# USB.net
KiCad netlist of a schematic drawn in Altium Designer
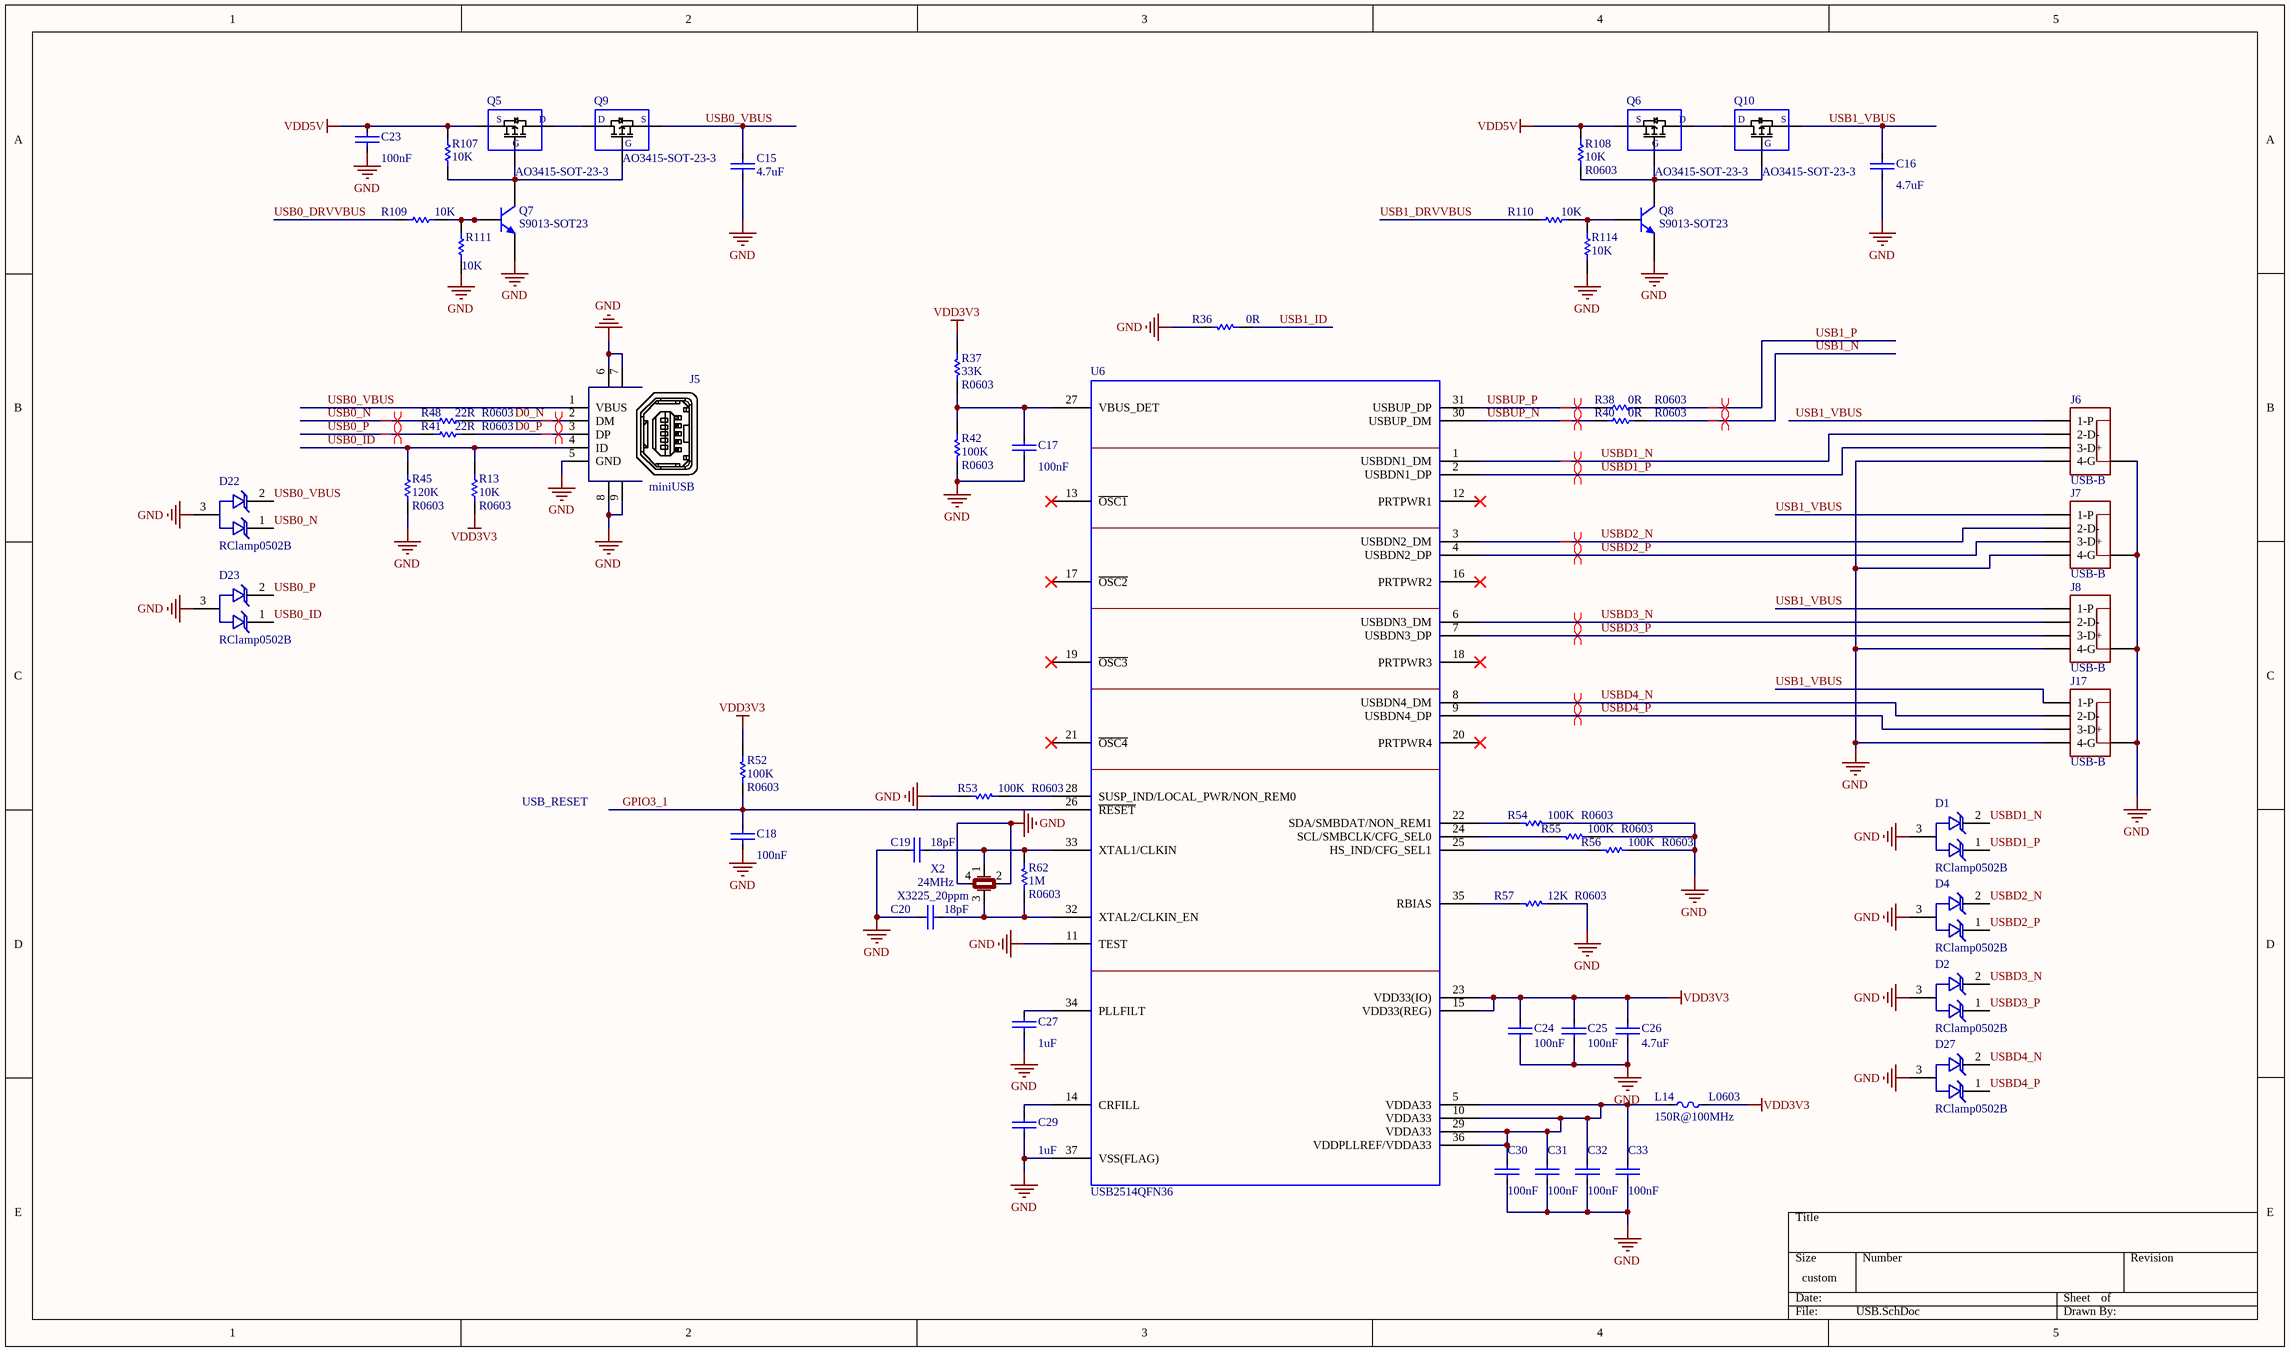
[diagram p0: USB.SchDoc]

(export (version "E")
  (design (tool "Eeschema 10.0.6"))
  (components
    (comp (ref "C15") (value "4.7uF") (footprint "C0603_M1608") (libsource (lib "OK335xD") (part "CAP_1")))
    (comp (ref "C16") (value "4.7uF") (footprint "C0603_M1608") (libsource (lib "OK335xD") (part "CAP_1")))
    (comp (ref "C17") (value "100nF") (footprint "C0603_M1608") (libsource (lib "OK335xD") (part "CAP_1")))
    (comp (ref "C18") (value "100nF") (footprint "C0603_M1608") (libsource (lib "OK335xD") (part "CAP_1")))
    (comp (ref "C19") (value "18pF") (footprint "C0603_M1608") (libsource (lib "OK335xD") (part "CAP_1")))
    (comp (ref "C20") (value "18pF") (footprint "C0603_M1608") (libsource (lib "OK335xD") (part "CAP_1")))
    (comp (ref "C23") (value "100nF") (footprint "C0603_M1608") (libsource (lib "OK335xD") (part "CAP_1")))
    (comp (ref "C24") (value "100nF") (footprint "C0603_M1608") (libsource (lib "OK335xD") (part "CAP_1")))
    (comp (ref "C25") (value "100nF") (footprint "C0603_M1608") (libsource (lib "OK335xD") (part "CAP_1")))
    (comp (ref "C26") (value "4.7uF") (footprint "C0603_M1608") (libsource (lib "OK335xD") (part "CAP_1")))
    (comp (ref "C27") (value "1uF") (footprint "C0603_M1608") (libsource (lib "OK335xD") (part "CAP_1")))
    (comp (ref "C29") (value "1uF") (footprint "C0603_M1608") (libsource (lib "OK335xD") (part "CAP_1")))
    (comp (ref "C30") (value "100nF") (footprint "C0603_M1608") (libsource (lib "OK335xD") (part "CAP_1")))
    (comp (ref "C31") (value "100nF") (footprint "C0603_M1608") (libsource (lib "OK335xD") (part "CAP_1")))
    (comp (ref "C32") (value "100nF") (footprint "C0603_M1608") (libsource (lib "OK335xD") (part "CAP_1")))
    (comp (ref "C33") (value "100nF") (footprint "C0603_M1608") (libsource (lib "OK335xD") (part "CAP_1")))
    (comp (ref "D1")
      (value "RClamp0502B")
      (footprint "SOT-523")
      (fields (field (name "Comment") "LCTVS"))
      (libsource (lib "Sch") (part "LCTVS"))
    )
    (comp (ref "D2")
      (value "RClamp0502B")
      (footprint "SOT-523")
      (fields (field (name "Comment") "LCTVS"))
      (libsource (lib "Sch") (part "LCTVS"))
    )
    (comp (ref "D4")
      (value "RClamp0502B")
      (footprint "SOT-523")
      (fields (field (name "Comment") "LCTVS"))
      (libsource (lib "Sch") (part "LCTVS"))
    )
    (comp (ref "D22")
      (value "RClamp0502B")
      (footprint "SOT-523")
      (fields (field (name "Comment") "LCTVS"))
      (libsource (lib "Sch") (part "LCTVS"))
    )
    (comp (ref "D23")
      (value "RClamp0502B")
      (footprint "SOT-523")
      (fields (field (name "Comment") "LCTVS"))
      (libsource (lib "Sch") (part "LCTVS"))
    )
    (comp (ref "D27")
      (value "RClamp0502B")
      (footprint "SOT-523")
      (fields (field (name "Comment") "LCTVS"))
      (libsource (lib "Sch") (part "LCTVS"))
    )
    (comp (ref "J5")
      (value "miniUSB")
      (footprint "MiniUSB")
      (libsource (lib "AM335X_bottom") (part "miniUSB"))
    )
    (comp (ref "J6") (value "USB-B") (footprint "USB-C") (libsource (lib "OK335xD") (part "USB_B")))
    (comp (ref "J7") (value "USB-B") (footprint "USB-C") (libsource (lib "OK335xD") (part "USB_B")))
    (comp (ref "J8") (value "USB-B") (footprint "USB-C") (libsource (lib "OK335xD") (part "USB_B")))
    (comp (ref "J17") (value "USB-B") (footprint "USB-C") (libsource (lib "OK335xD") (part "USB_B")))
    (comp (ref "L14")
      (value "150R@100MHz")
      (footprint "L0603_M1608")
      (description "0603")
      (fields (field (name "ALTIUM_VALUE") "L0603"))
      (libsource (lib "S5PV210_core") (part "BEADS"))
    )
    (comp (ref "Q5")
      (value "AO3415-SOT-23-3")
      (footprint "SOT23")
      (libsource (lib "OK335xD") (part "AO3415"))
    )
    (comp (ref "Q6")
      (value "AO3415-SOT-23-3")
      (footprint "SOT23")
      (libsource (lib "OK335xD") (part "AO3415"))
    )
    (comp (ref "Q7") (value "S9013-SOT23") (footprint "SOT23") (libsource (lib "Sch") (part "S9013")))
    (comp (ref "Q8") (value "S9013-SOT23") (footprint "SOT23") (libsource (lib "Sch") (part "S9013")))
    (comp (ref "Q9")
      (value "AO3415-SOT-23-3")
      (footprint "SOT23")
      (libsource (lib "OK335xD") (part "AO3415"))
    )
    (comp (ref "Q10")
      (value "AO3415-SOT-23-3")
      (footprint "SOT23")
      (libsource (lib "OK335xD") (part "AO3415"))
    )
    (comp (ref "R13")
      (value "10K")
      (footprint "R0603_M1608")
      (description "R0603")
      (fields (field (name "ALTIUM_VALUE") "R0603") (field (name "PUBLISHER") "Altium Limited"))
      (libsource (lib "Miscellaneous Devices") (part "Res1"))
    )
    (comp (ref "R36")
      (value "0R")
      (footprint "R0603_M1608")
      (description "R0603")
      (fields (field (name "PUBLISHER") "Altium Limited"))
      (libsource (lib "Miscellaneous Devices") (part "Res1"))
    )
    (comp (ref "R37")
      (value "33K")
      (footprint "R0603_M1608")
      (description "R0603")
      (fields (field (name "ALTIUM_VALUE") "R0603") (field (name "PUBLISHER") "Altium Limited"))
      (libsource (lib "Miscellaneous Devices") (part "Res1"))
    )
    (comp (ref "R38")
      (value "0R")
      (footprint "R0603_M1608")
      (description "R0603")
      (fields (field (name "ALTIUM_VALUE") "R0603") (field (name "PUBLISHER") "Altium Limited"))
      (libsource (lib "Miscellaneous Devices") (part "Res1"))
    )
    (comp (ref "R40")
      (value "0R")
      (footprint "R0603_M1608")
      (description "R0603")
      (fields (field (name "ALTIUM_VALUE") "R0603") (field (name "PUBLISHER") "Altium Limited"))
      (libsource (lib "Miscellaneous Devices") (part "Res1"))
    )
    (comp (ref "R41")
      (value "22R")
      (footprint "R0603_M1608")
      (description "R0603")
      (fields (field (name "ALTIUM_VALUE") "R0603") (field (name "PUBLISHER") "Altium Limited"))
      (libsource (lib "Miscellaneous Devices") (part "Res1"))
    )
    (comp (ref "R42")
      (value "100K")
      (footprint "R0603_M1608")
      (description "R0603")
      (fields (field (name "ALTIUM_VALUE") "R0603") (field (name "PUBLISHER") "Altium Limited"))
      (libsource (lib "Miscellaneous Devices") (part "Res1"))
    )
    (comp (ref "R45")
      (value "120K")
      (footprint "R0603_M1608")
      (description "R0603")
      (fields (field (name "ALTIUM_VALUE") "R0603") (field (name "PUBLISHER") "Altium Limited"))
      (libsource (lib "Miscellaneous Devices") (part "Res1"))
    )
    (comp (ref "R48")
      (value "22R")
      (footprint "R0603_M1608")
      (description "R0603")
      (fields (field (name "ALTIUM_VALUE") "R0603") (field (name "PUBLISHER") "Altium Limited"))
      (libsource (lib "Miscellaneous Devices") (part "Res1"))
    )
    (comp (ref "R52")
      (value "100K")
      (footprint "R0603_M1608")
      (description "R0603")
      (fields (field (name "ALTIUM_VALUE") "R0603") (field (name "PUBLISHER") "Altium Limited"))
      (libsource (lib "Miscellaneous Devices") (part "Res1"))
    )
    (comp (ref "R53")
      (value "100K")
      (footprint "R0603_M1608")
      (description "R0603")
      (fields (field (name "ALTIUM_VALUE") "R0603") (field (name "PUBLISHER") "Altium Limited"))
      (libsource (lib "Miscellaneous Devices") (part "Res1"))
    )
    (comp (ref "R54")
      (value "100K")
      (footprint "R0603_M1608")
      (description "R0603")
      (fields (field (name "ALTIUM_VALUE") "R0603") (field (name "PUBLISHER") "Altium Limited"))
      (libsource (lib "Miscellaneous Devices") (part "Res1"))
    )
    (comp (ref "R55")
      (value "100K")
      (footprint "R0603_M1608")
      (description "R0603")
      (fields (field (name "ALTIUM_VALUE") "R0603") (field (name "PUBLISHER") "Altium Limited"))
      (libsource (lib "Miscellaneous Devices") (part "Res1"))
    )
    (comp (ref "R56")
      (value "100K")
      (footprint "R0603_M1608")
      (description "R0603")
      (fields (field (name "ALTIUM_VALUE") "R0603") (field (name "PUBLISHER") "Altium Limited"))
      (libsource (lib "Miscellaneous Devices") (part "Res1"))
    )
    (comp (ref "R57")
      (value "12K")
      (footprint "R0603_M1608")
      (description "R0603")
      (fields (field (name "ALTIUM_VALUE") "R0603") (field (name "PUBLISHER") "Altium Limited"))
      (libsource (lib "Miscellaneous Devices") (part "Res1"))
    )
    (comp (ref "R62")
      (value "1M")
      (footprint "R0603_M1608")
      (description "R0603")
      (fields (field (name "ALTIUM_VALUE") "R0603") (field (name "PUBLISHER") "Altium Limited"))
      (libsource (lib "Miscellaneous Devices") (part "Res1"))
    )
    (comp (ref "R107")
      (value "10K")
      (footprint "R0603_M1608")
      (description "R0603")
      (fields (field (name "PUBLISHER") "Altium Limited"))
      (libsource (lib "Miscellaneous Devices") (part "Res1"))
    )
    (comp (ref "R108")
      (value "10K")
      (footprint "R0603_M1608")
      (description "R0603")
      (fields (field (name "ALTIUM_VALUE") "R0603") (field (name "PUBLISHER") "Altium Limited"))
      (libsource (lib "Miscellaneous Devices") (part "Res1"))
    )
    (comp (ref "R109")
      (value "10K")
      (footprint "R0603_M1608")
      (description "R0603")
      (fields (field (name "PUBLISHER") "Altium Limited"))
      (libsource (lib "Miscellaneous Devices") (part "Res1"))
    )
    (comp (ref "R110")
      (value "10K")
      (footprint "R0603_M1608")
      (description "R0603")
      (fields (field (name "PUBLISHER") "Altium Limited"))
      (libsource (lib "Miscellaneous Devices") (part "Res1"))
    )
    (comp (ref "R111")
      (value "10K")
      (footprint "R0603_M1608")
      (description "R0603")
      (fields (field (name "PUBLISHER") "Altium Limited"))
      (libsource (lib "Miscellaneous Devices") (part "Res1"))
    )
    (comp (ref "R114")
      (value "10K")
      (footprint "R0603_M1608")
      (description "R0603")
      (fields (field (name "PUBLISHER") "Altium Limited"))
      (libsource (lib "Miscellaneous Devices") (part "Res1"))
    )
    (comp (ref "U6")
      (value "USB2514QFN36")
      (footprint "QFN36(USB251x)")
      (libsource (lib "OK335xD") (part "USB2514QFN36"))
    )
    (comp (ref "X2")
      (value "24MHz")
      (footprint "Crystals_3225")
      (description "X3225_20ppm")
      (fields (field (name "ALTIUM_VALUE") "X3225_20ppm"))
      (libsource (lib "S5PV210_core") (part "XTAL"))
    )
  )
  (nets
    (net (code "1") (name "/D0_N") (class "Default")
      (node (ref "J5") (pin "2") (pinfunction "DM_2") (pintype "passive"))
      (node (ref "R48") (pin "2") (pinfunction "2_2") (pintype "passive"))
    )
    (net (code "2") (name "/D0_P") (class "Default")
      (node (ref "J5") (pin "3") (pinfunction "DP_3") (pintype "passive"))
      (node (ref "R41") (pin "2") (pinfunction "2_2") (pintype "passive"))
    )
    (net (code "3") (name "/GPIO3_1") (class "Default")
      (node (ref "C18") (pin "2") (pintype "passive"))
      (node (ref "R52") (pin "1") (pinfunction "1_1") (pintype "passive"))
      (node (ref "U6") (pin "26") (pinfunction "~{RESET}_26") (pintype "passive"))
    )
    (net (code "4") (name "/USB0_DRVVBUS") (class "Default")
      (node (ref "R109") (pin "2") (pinfunction "2_2") (pintype "passive"))
    )
    (net (code "5") (name "/USB0_ID") (class "Default")
      (node (ref "D23") (pin "1") (pinfunction "1_1") (pintype "passive"))
      (node (ref "J5") (pin "4") (pinfunction "ID_4") (pintype "passive"))
      (node (ref "R13") (pin "2") (pinfunction "2_2") (pintype "passive"))
      (node (ref "R45") (pin "2") (pinfunction "2_2") (pintype "passive"))
    )
    (net (code "6") (name "/USB0_N") (class "Default")
      (node (ref "D22") (pin "1") (pinfunction "1_1") (pintype "passive"))
      (node (ref "R48") (pin "1") (pinfunction "1_1") (pintype "passive"))
    )
    (net (code "7") (name "/USB0_P") (class "Default")
      (node (ref "D23") (pin "2") (pinfunction "2_2") (pintype "passive"))
      (node (ref "R41") (pin "1") (pinfunction "1_1") (pintype "passive"))
    )
    (net (code "8") (name "/USB0_VBUS") (class "Default")
      (node (ref "C15") (pin "1") (pintype "passive"))
      (node (ref "D22") (pin "2") (pinfunction "2_2") (pintype "passive"))
      (node (ref "J5") (pin "1") (pinfunction "VBUS_1") (pintype "passive"))
      (node (ref "Q9") (pin "2") (pinfunction "S_2") (pintype "passive"))
    )
    (net (code "9") (name "/USB1_DRVVBUS") (class "Default")
      (node (ref "R110") (pin "2") (pinfunction "2_2") (pintype "passive"))
    )
    (net (code "10") (name "/USB1_ID") (class "Default")
      (node (ref "R36") (pin "2") (pinfunction "2_2") (pintype "passive"))
    )
    (net (code "11") (name "/USB1_N") (class "Default")
      (node (ref "R40") (pin "2") (pinfunction "2_2") (pintype "passive"))
    )
    (net (code "12") (name "/USB1_P") (class "Default")
      (node (ref "R38") (pin "2") (pinfunction "2_2") (pintype "passive"))
    )
    (net (code "13") (name "/USB1_VBUS") (class "Default")
      (node (ref "C16") (pin "1") (pintype "passive"))
      (node (ref "J17") (pin "1") (pinfunction "1-P_1") (pintype "passive"))
      (node (ref "J6") (pin "1") (pinfunction "1-P_1") (pintype "passive"))
      (node (ref "J7") (pin "1") (pinfunction "1-P_1") (pintype "passive"))
      (node (ref "J8") (pin "1") (pinfunction "1-P_1") (pintype "passive"))
      (node (ref "Q10") (pin "2") (pinfunction "S_2") (pintype "passive"))
    )
    (net (code "14") (name "/USBD1_N") (class "Default")
      (node (ref "D1") (pin "2") (pinfunction "2_2") (pintype "passive"))
      (node (ref "J6") (pin "2") (pinfunction "2-D-_2") (pintype "passive"))
      (node (ref "U6") (pin "1") (pinfunction "USBDN1_DM_1") (pintype "passive"))
    )
    (net (code "15") (name "/USBD1_P") (class "Default")
      (node (ref "D1") (pin "1") (pinfunction "1_1") (pintype "passive"))
      (node (ref "J6") (pin "3") (pinfunction "3-D+_3") (pintype "passive"))
      (node (ref "U6") (pin "2") (pinfunction "USBDN1_DP_2") (pintype "passive"))
    )
    (net (code "16") (name "/USBD2_N") (class "Default")
      (node (ref "D4") (pin "2") (pinfunction "2_2") (pintype "passive"))
      (node (ref "J7") (pin "2") (pinfunction "2-D-_2") (pintype "passive"))
      (node (ref "U6") (pin "3") (pinfunction "USBDN2_DM_3") (pintype "passive"))
    )
    (net (code "17") (name "/USBD2_P") (class "Default")
      (node (ref "D4") (pin "1") (pinfunction "1_1") (pintype "passive"))
      (node (ref "J7") (pin "3") (pinfunction "3-D+_3") (pintype "passive"))
      (node (ref "U6") (pin "4") (pinfunction "USBDN2_DP_4") (pintype "passive"))
    )
    (net (code "18") (name "/USBD3_N") (class "Default")
      (node (ref "D2") (pin "2") (pinfunction "2_2") (pintype "passive"))
      (node (ref "J8") (pin "2") (pinfunction "2-D-_2") (pintype "passive"))
      (node (ref "U6") (pin "6") (pinfunction "USBDN3_DM_6") (pintype "passive"))
    )
    (net (code "19") (name "/USBD3_P") (class "Default")
      (node (ref "D2") (pin "1") (pinfunction "1_1") (pintype "passive"))
      (node (ref "J8") (pin "3") (pinfunction "3-D+_3") (pintype "passive"))
      (node (ref "U6") (pin "7") (pinfunction "USBDN3_DP_7") (pintype "passive"))
    )
    (net (code "20") (name "/USBD4_N") (class "Default")
      (node (ref "D27") (pin "2") (pinfunction "2_2") (pintype "passive"))
      (node (ref "J17") (pin "2") (pinfunction "2-D-_2") (pintype "passive"))
      (node (ref "U6") (pin "8") (pinfunction "USBDN4_DM_8") (pintype "passive"))
    )
    (net (code "21") (name "/USBD4_P") (class "Default")
      (node (ref "D27") (pin "1") (pinfunction "1_1") (pintype "passive"))
      (node (ref "J17") (pin "3") (pinfunction "3-D+_3") (pintype "passive"))
      (node (ref "U6") (pin "9") (pinfunction "USBDN4_DP_9") (pintype "passive"))
    )
    (net (code "22") (name "/USBUP_N") (class "Default")
      (node (ref "R40") (pin "1") (pinfunction "1_1") (pintype "passive"))
      (node (ref "U6") (pin "30") (pinfunction "USBUP_DM_30") (pintype "passive"))
    )
    (net (code "23") (name "/USBUP_P") (class "Default")
      (node (ref "R38") (pin "1") (pinfunction "1_1") (pintype "passive"))
      (node (ref "U6") (pin "31") (pinfunction "USBUP_DP_31") (pintype "passive"))
    )
    (net (code "24") (name "GND") (class "Default")
      (node (ref "C15") (pin "2") (pintype "passive"))
      (node (ref "C16") (pin "2") (pintype "passive"))
      (node (ref "C17") (pin "2") (pintype "passive"))
      (node (ref "C18") (pin "1") (pintype "passive"))
      (node (ref "C19") (pin "1") (pintype "passive"))
      (node (ref "C20") (pin "1") (pintype "passive"))
      (node (ref "C23") (pin "1") (pintype "passive"))
      (node (ref "C24") (pin "2") (pintype "passive"))
      (node (ref "C25") (pin "2") (pintype "passive"))
      (node (ref "C26") (pin "2") (pintype "passive"))
      (node (ref "C27") (pin "2") (pintype "passive"))
      (node (ref "C29") (pin "2") (pintype "passive"))
      (node (ref "C30") (pin "2") (pintype "passive"))
      (node (ref "C31") (pin "2") (pintype "passive"))
      (node (ref "C32") (pin "2") (pintype "passive"))
      (node (ref "C33") (pin "2") (pintype "passive"))
      (node (ref "D1") (pin "3") (pintype "passive"))
      (node (ref "D2") (pin "3") (pintype "passive"))
      (node (ref "D22") (pin "3") (pintype "passive"))
      (node (ref "D23") (pin "3") (pintype "passive"))
      (node (ref "D27") (pin "3") (pintype "passive"))
      (node (ref "D4") (pin "3") (pintype "passive"))
      (node (ref "J17") (pin "0") (pinfunction "0_0") (pintype "passive"))
      (node (ref "J17") (pin "4") (pinfunction "4-G_4") (pintype "passive"))
      (node (ref "J5") (pin "5") (pinfunction "GND_5") (pintype "passive"))
      (node (ref "J5") (pin "6") (pinfunction "6_6") (pintype "passive"))
      (node (ref "J5") (pin "7") (pinfunction "7_7") (pintype "passive"))
      (node (ref "J5") (pin "8") (pinfunction "8_8") (pintype "passive"))
      (node (ref "J5") (pin "9") (pinfunction "9_9") (pintype "passive"))
      (node (ref "J6") (pin "0") (pinfunction "0_0") (pintype "passive"))
      (node (ref "J6") (pin "4") (pinfunction "4-G_4") (pintype "passive"))
      (node (ref "J7") (pin "0") (pinfunction "0_0") (pintype "passive"))
      (node (ref "J7") (pin "4") (pinfunction "4-G_4") (pintype "passive"))
      (node (ref "J8") (pin "0") (pinfunction "0_0") (pintype "passive"))
      (node (ref "J8") (pin "4") (pinfunction "4-G_4") (pintype "passive"))
      (node (ref "Q7") (pin "2") (pinfunction "E_2") (pintype "passive"))
      (node (ref "Q8") (pin "2") (pinfunction "E_2") (pintype "passive"))
      (node (ref "R111") (pin "2") (pinfunction "2_2") (pintype "passive"))
      (node (ref "R114") (pin "2") (pinfunction "2_2") (pintype "passive"))
      (node (ref "R36") (pin "1") (pinfunction "1_1") (pintype "passive"))
      (node (ref "R42") (pin "1") (pinfunction "1_1") (pintype "passive"))
      (node (ref "R45") (pin "1") (pinfunction "1_1") (pintype "passive"))
      (node (ref "R53") (pin "1") (pinfunction "1_1") (pintype "passive"))
      (node (ref "R54") (pin "2") (pinfunction "2_2") (pintype "passive"))
      (node (ref "R55") (pin "2") (pinfunction "2_2") (pintype "passive"))
      (node (ref "R56") (pin "2") (pinfunction "2_2") (pintype "passive"))
      (node (ref "R57") (pin "2") (pinfunction "2_2") (pintype "passive"))
      (node (ref "U6") (pin "11") (pinfunction "TEST_11") (pintype "passive"))
      (node (ref "U6") (pin "37") (pinfunction "VSS(FLAG)_37") (pintype "passive"))
      (node (ref "X2") (pin "2") (pinfunction "2_2") (pintype "passive"))
      (node (ref "X2") (pin "4") (pinfunction "4_4") (pintype "passive"))
    )
    (net (code "25") (name "Net-(Q5-D)") (class "Default")
      (node (ref "Q5") (pin "3") (pinfunction "D_3") (pintype "passive"))
      (node (ref "Q9") (pin "3") (pinfunction "D_3") (pintype "passive"))
    )
    (net (code "26") (name "Net-(Q5-G)") (class "Default")
      (node (ref "Q5") (pin "1") (pinfunction "G_1") (pintype "passive"))
      (node (ref "Q7") (pin "3") (pinfunction "C_3") (pintype "passive"))
      (node (ref "Q9") (pin "1") (pinfunction "G_1") (pintype "passive"))
      (node (ref "R107") (pin "1") (pinfunction "1_1") (pintype "passive"))
    )
    (net (code "27") (name "Net-(Q7-B)") (class "Default")
      (node (ref "Q7") (pin "1") (pinfunction "B_1") (pintype "passive"))
      (node (ref "R109") (pin "1") (pinfunction "1_1") (pintype "passive"))
      (node (ref "R111") (pin "1") (pinfunction "1_1") (pintype "passive"))
    )
    (net (code "28") (name "Net-(Q8-B)") (class "Default")
      (node (ref "Q8") (pin "1") (pinfunction "B_1") (pintype "passive"))
      (node (ref "R110") (pin "1") (pinfunction "1_1") (pintype "passive"))
      (node (ref "R114") (pin "1") (pinfunction "1_1") (pintype "passive"))
    )
    (net (code "29") (name "Net-(Q10-D)") (class "Default")
      (node (ref "Q10") (pin "3") (pinfunction "D_3") (pintype "passive"))
      (node (ref "Q6") (pin "3") (pinfunction "D_3") (pintype "passive"))
    )
    (net (code "30") (name "Net-(Q10-G)") (class "Default")
      (node (ref "Q10") (pin "1") (pinfunction "G_1") (pintype "passive"))
      (node (ref "Q6") (pin "1") (pinfunction "G_1") (pintype "passive"))
      (node (ref "Q8") (pin "3") (pinfunction "C_3") (pintype "passive"))
      (node (ref "R108") (pin "1") (pinfunction "1_1") (pintype "passive"))
    )
    (net (code "31") (name "Net-(U6-CRFILL)") (class "Default")
      (node (ref "C29") (pin "1") (pintype "passive"))
      (node (ref "U6") (pin "14") (pinfunction "CRFILL_14") (pintype "passive"))
    )
    (net (code "32") (name "Net-(U6-HS_IND{slash}CFG_SEL1)") (class "Default")
      (node (ref "R56") (pin "1") (pinfunction "1_1") (pintype "passive"))
      (node (ref "U6") (pin "25") (pinfunction "HS_IND/CFG_SEL1_25") (pintype "passive"))
    )
    (net (code "33") (name "Net-(U6-PLLFILT)") (class "Default")
      (node (ref "C27") (pin "1") (pintype "passive"))
      (node (ref "U6") (pin "34") (pinfunction "PLLFILT_34") (pintype "passive"))
    )
    (net (code "34") (name "Net-(U6-RBIAS)") (class "Default")
      (node (ref "R57") (pin "1") (pinfunction "1_1") (pintype "passive"))
      (node (ref "U6") (pin "35") (pinfunction "RBIAS_35") (pintype "passive"))
    )
    (net (code "35") (name "Net-(U6-SCL{slash}SMBCLK{slash}CFG_SEL0)") (class "Default")
      (node (ref "R55") (pin "1") (pinfunction "1_1") (pintype "passive"))
      (node (ref "U6") (pin "24") (pinfunction "SCL/SMBCLK/CFG_SEL0_24") (pintype "passive"))
    )
    (net (code "36") (name "Net-(U6-SDA{slash}SMBDAT{slash}NON_REM1)") (class "Default")
      (node (ref "R54") (pin "1") (pinfunction "1_1") (pintype "passive"))
      (node (ref "U6") (pin "22") (pinfunction "SDA/SMBDAT/NON_REM1_22") (pintype "passive"))
    )
    (net (code "37") (name "Net-(U6-SUSP_IND{slash}LOCAL_PWR{slash}NON_REM0)") (class "Default")
      (node (ref "R53") (pin "2") (pinfunction "2_2") (pintype "passive"))
      (node (ref "U6") (pin "28") (pinfunction "SUSP_IND/LOCAL_PWR/NON_REM0_28") (pintype "passive"))
    )
    (net (code "38") (name "Net-(U6-VBUS_DET)") (class "Default")
      (node (ref "C17") (pin "1") (pintype "passive"))
      (node (ref "R37") (pin "1") (pinfunction "1_1") (pintype "passive"))
      (node (ref "R42") (pin "2") (pinfunction "2_2") (pintype "passive"))
      (node (ref "U6") (pin "27") (pinfunction "VBUS_DET_27") (pintype "passive"))
    )
    (net (code "39") (name "Net-(U6-VDDPLLREF{slash}VDDA33)") (class "Default")
      (node (ref "C30") (pin "1") (pintype "passive"))
      (node (ref "C31") (pin "1") (pintype "passive"))
      (node (ref "C32") (pin "1") (pintype "passive"))
      (node (ref "C33") (pin "1") (pintype "passive"))
      (node (ref "L14") (pin "2") (pinfunction "2_2") (pintype "passive"))
      (node (ref "U6") (pin "10") (pinfunction "VDDA33_10") (pintype "passive"))
      (node (ref "U6") (pin "29") (pinfunction "VDDA33_29") (pintype "passive"))
      (node (ref "U6") (pin "36") (pinfunction "VDDPLLREF/VDDA33_36") (pintype "passive"))
      (node (ref "U6") (pin "5") (pinfunction "VDDA33_5") (pintype "passive"))
    )
    (net (code "40") (name "Net-(U6-XTAL1{slash}CLKIN)") (class "Default")
      (node (ref "C19") (pin "2") (pintype "passive"))
      (node (ref "R62") (pin "2") (pinfunction "2_2") (pintype "passive"))
      (node (ref "U6") (pin "33") (pinfunction "XTAL1/CLKIN_33") (pintype "passive"))
      (node (ref "X2") (pin "1") (pinfunction "1_1") (pintype "passive"))
    )
    (net (code "41") (name "Net-(U6-XTAL2{slash}CLKIN_EN)") (class "Default")
      (node (ref "C20") (pin "2") (pintype "passive"))
      (node (ref "R62") (pin "1") (pinfunction "1_1") (pintype "passive"))
      (node (ref "U6") (pin "32") (pinfunction "XTAL2/CLKIN_EN_32") (pintype "passive"))
      (node (ref "X2") (pin "3") (pinfunction "3_3") (pintype "passive"))
    )
    (net (code "42") (name "VDD3V3") (class "Default")
      (node (ref "C24") (pin "1") (pintype "passive"))
      (node (ref "C25") (pin "1") (pintype "passive"))
      (node (ref "C26") (pin "1") (pintype "passive"))
      (node (ref "L14") (pin "1") (pinfunction "1_1") (pintype "passive"))
      (node (ref "R13") (pin "1") (pinfunction "1_1") (pintype "passive"))
      (node (ref "R37") (pin "2") (pinfunction "2_2") (pintype "passive"))
      (node (ref "R52") (pin "2") (pinfunction "2_2") (pintype "passive"))
      (node (ref "U6") (pin "15") (pinfunction "VDD33(REG)_15") (pintype "passive"))
      (node (ref "U6") (pin "23") (pinfunction "VDD33(IO)_23") (pintype "passive"))
    )
    (net (code "43") (name "VDD5V") (class "Default")
      (node (ref "C23") (pin "2") (pintype "passive"))
      (node (ref "Q5") (pin "2") (pinfunction "S_2") (pintype "passive"))
      (node (ref "Q6") (pin "2") (pinfunction "S_2") (pintype "passive"))
      (node (ref "R107") (pin "2") (pinfunction "2_2") (pintype "passive"))
      (node (ref "R108") (pin "2") (pinfunction "2_2") (pintype "passive"))
    )
    (net (code "44") (name "unconnected-(U6-PRTPWR1-Pad12)") (class "Default")
      (node (ref "U6") (pin "12") (pinfunction "PRTPWR1_12") (pintype "passive+no_connect"))
    )
    (net (code "45") (name "unconnected-(U6-PRTPWR2-Pad16)") (class "Default")
      (node (ref "U6") (pin "16") (pinfunction "PRTPWR2_16") (pintype "passive+no_connect"))
    )
    (net (code "46") (name "unconnected-(U6-PRTPWR3-Pad18)") (class "Default")
      (node (ref "U6") (pin "18") (pinfunction "PRTPWR3_18") (pintype "passive+no_connect"))
    )
    (net (code "47") (name "unconnected-(U6-PRTPWR4-Pad20)") (class "Default")
      (node (ref "U6") (pin "20") (pinfunction "PRTPWR4_20") (pintype "passive+no_connect"))
    )
    (net (code "48") (name "unconnected-(U6-~{OSC1}-Pad13)") (class "Default")
      (node (ref "U6") (pin "13") (pinfunction "~{OSC1}_13") (pintype "passive+no_connect"))
    )
    (net (code "49") (name "unconnected-(U6-~{OSC2}-Pad17)") (class "Default")
      (node (ref "U6") (pin "17") (pinfunction "~{OSC2}_17") (pintype "passive+no_connect"))
    )
    (net (code "50") (name "unconnected-(U6-~{OSC3}-Pad19)") (class "Default")
      (node (ref "U6") (pin "19") (pinfunction "~{OSC3}_19") (pintype "passive+no_connect"))
    )
    (net (code "51") (name "unconnected-(U6-~{OSC4}-Pad21)") (class "Default")
      (node (ref "U6") (pin "21") (pinfunction "~{OSC4}_21") (pintype "passive+no_connect"))
    )
  )
)
